# ODB21.net
KiCad netlist of a schematic drawn in EAGLE
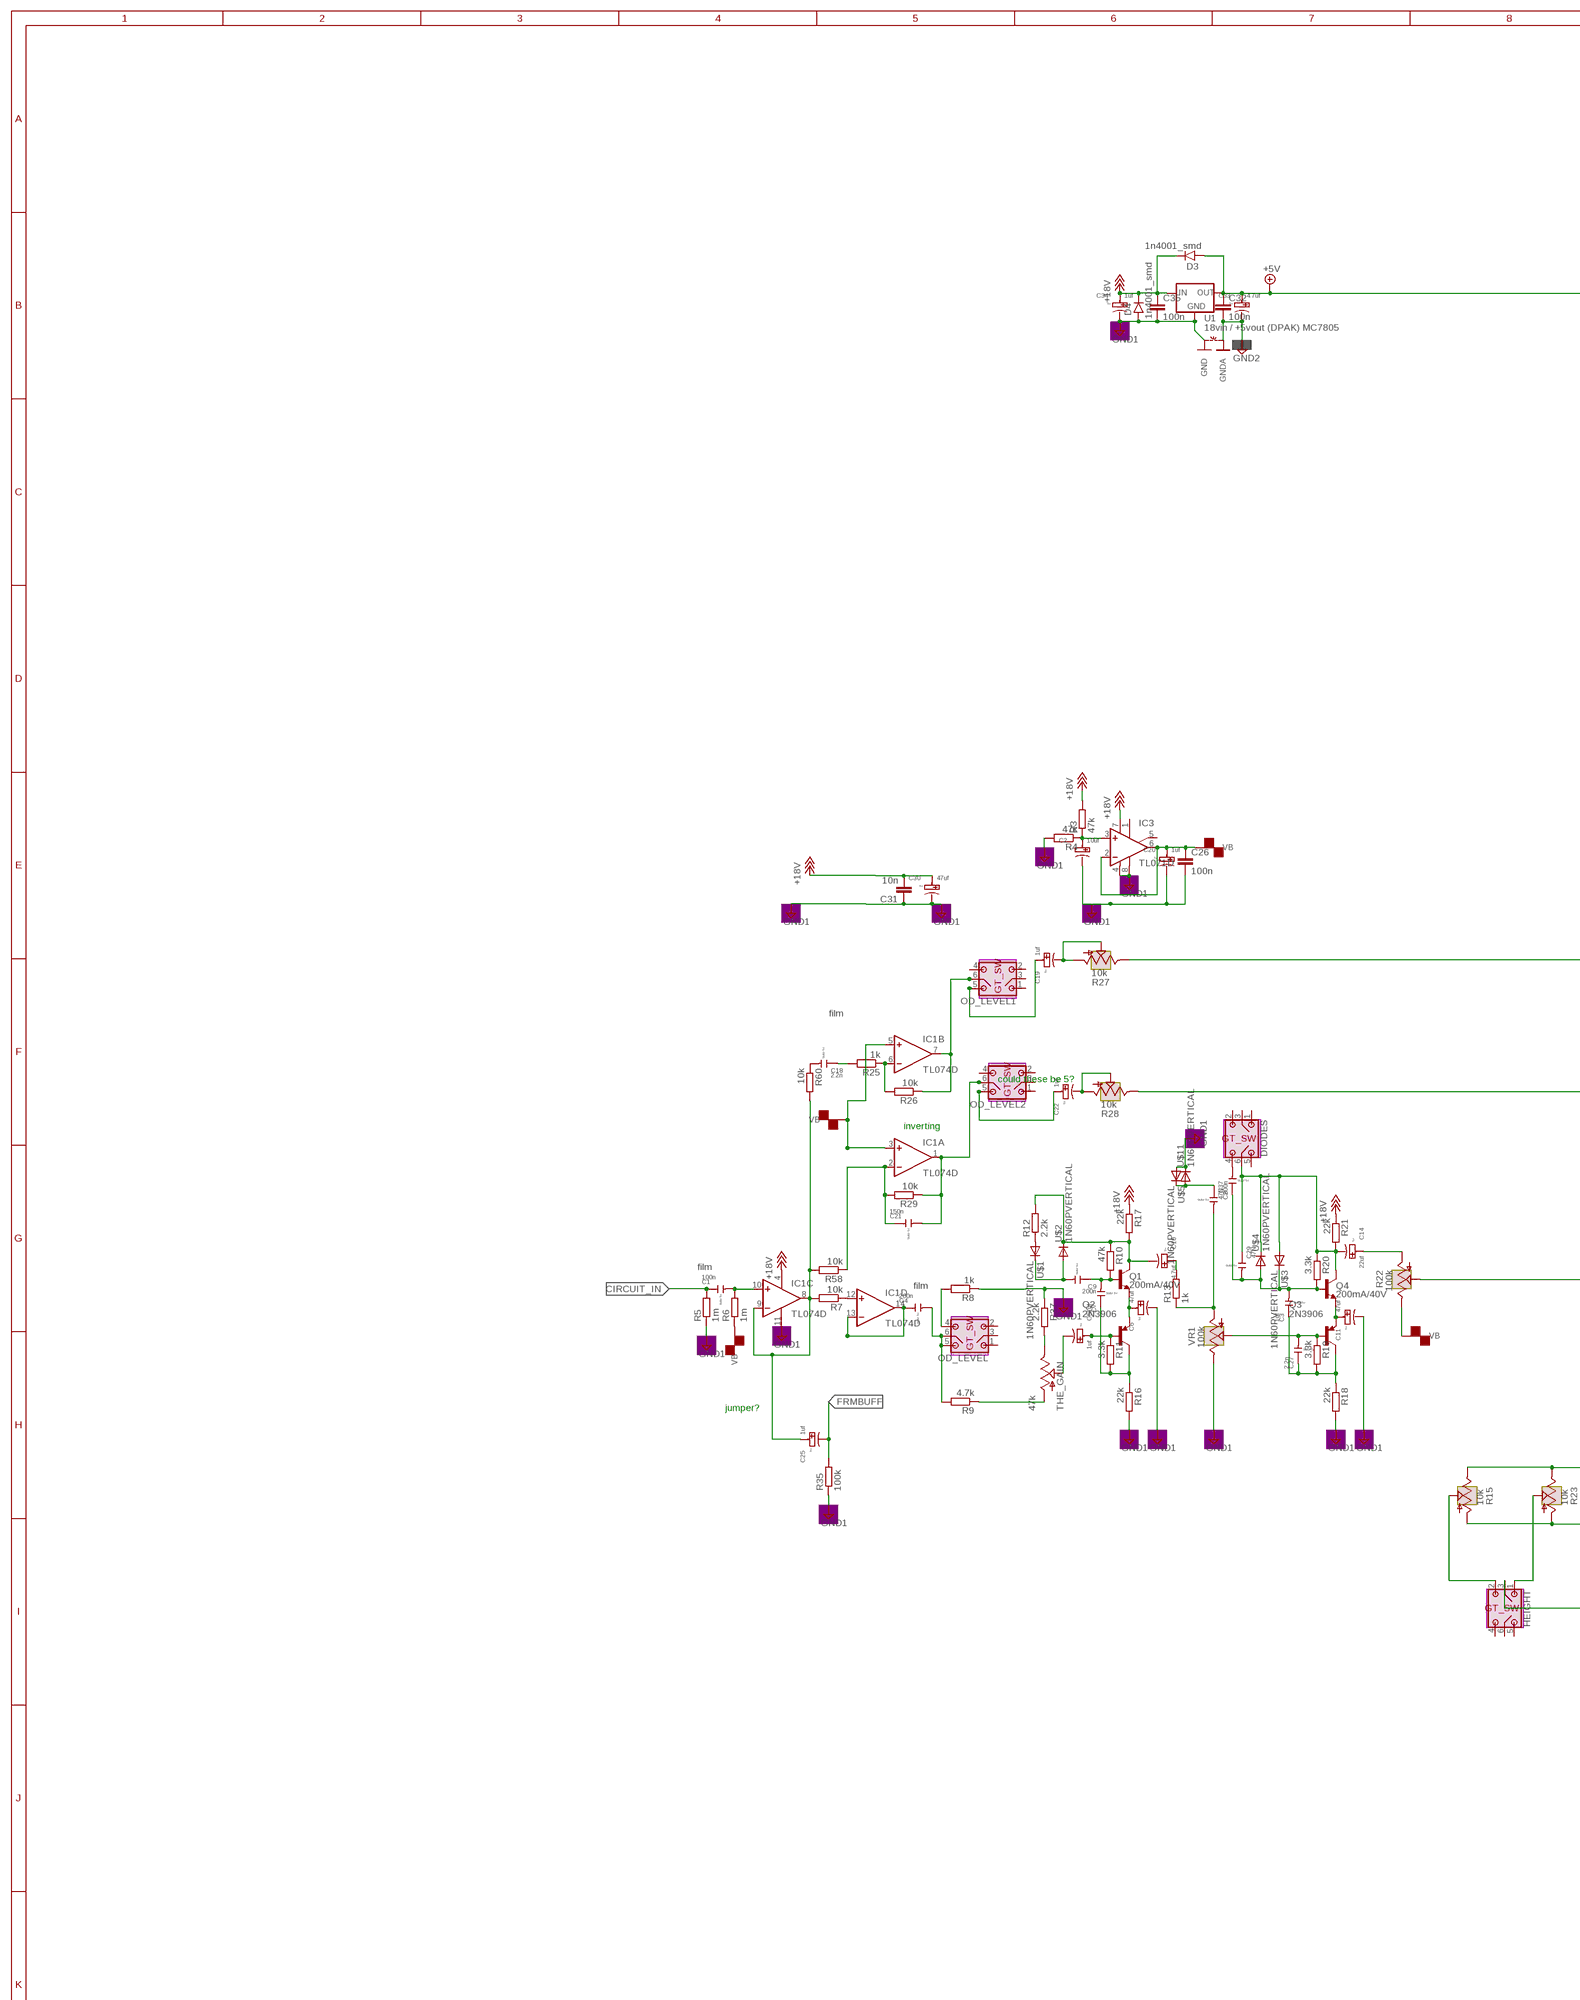
[diagram p0: schematic, sheet 1, part 1 of 3]
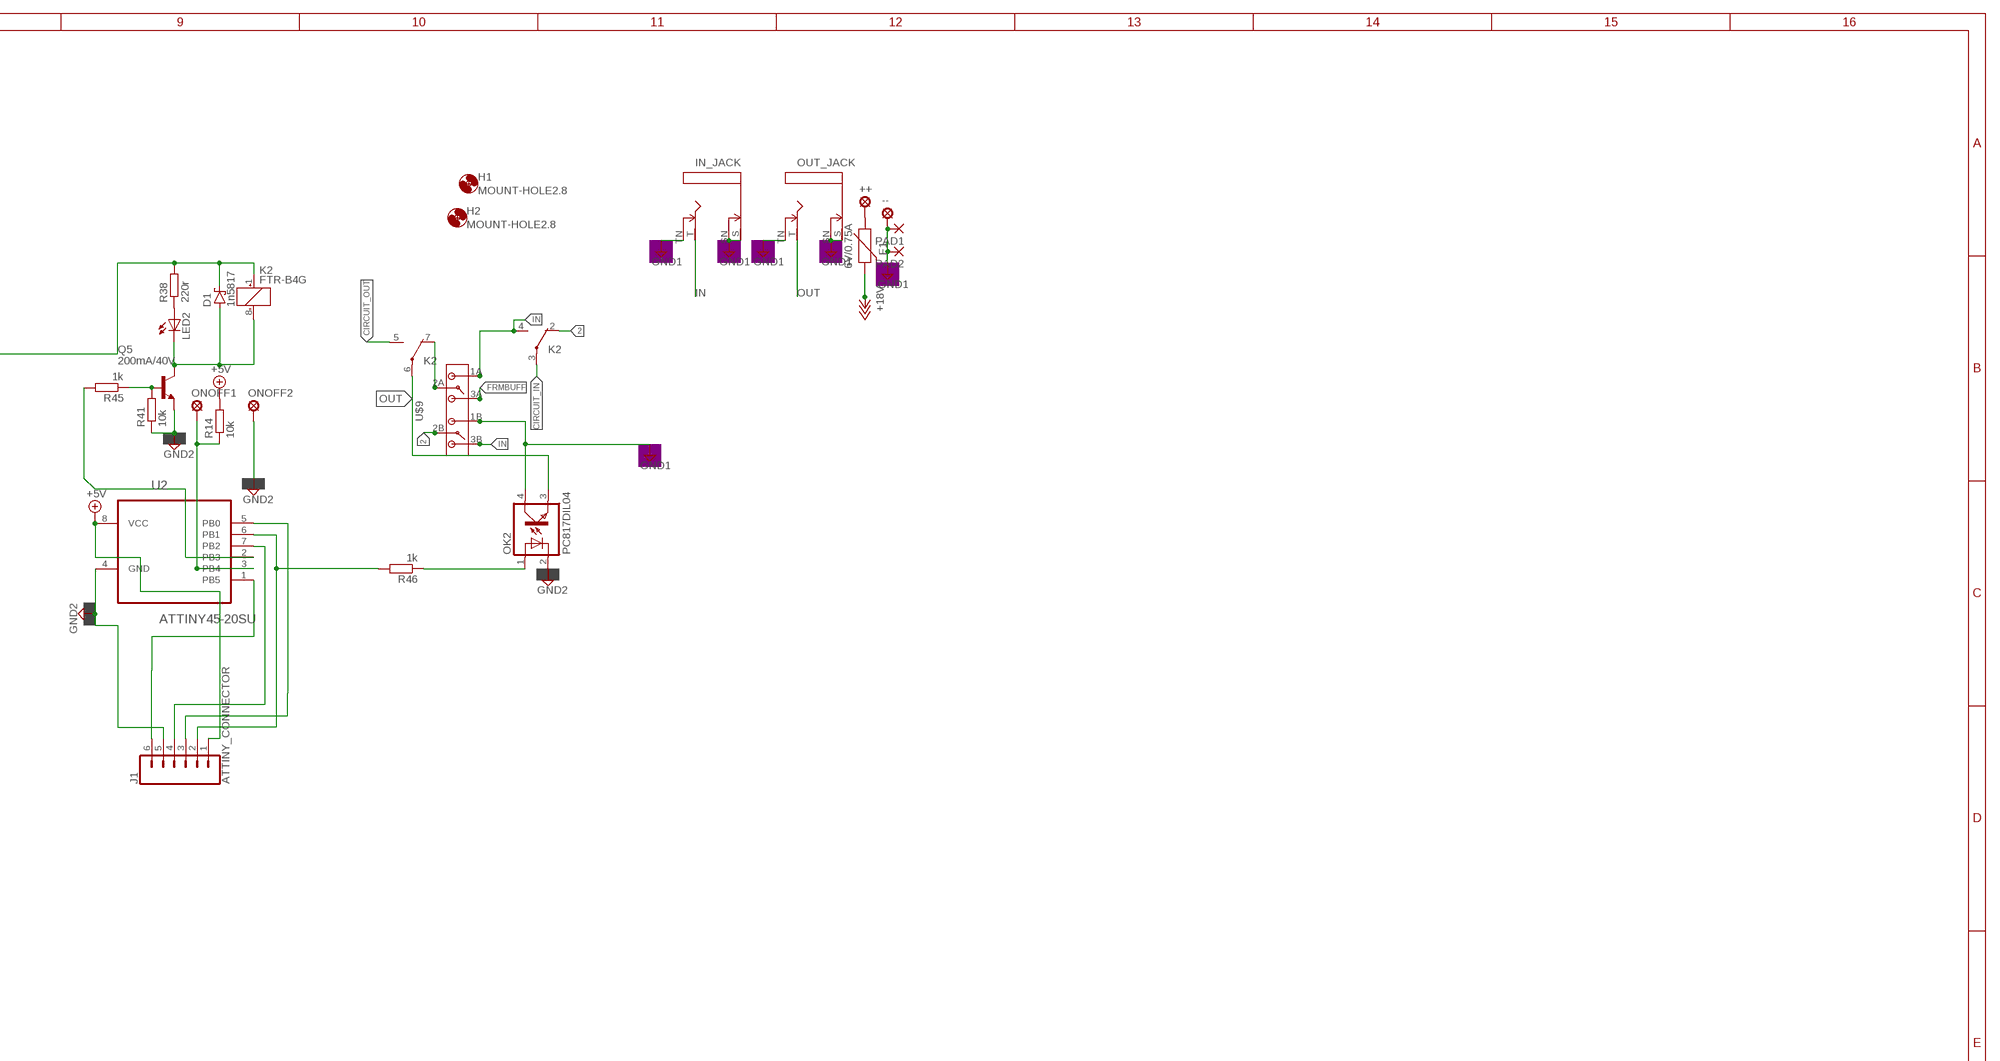
[diagram p1: schematic, sheet 1, part 2 of 3]
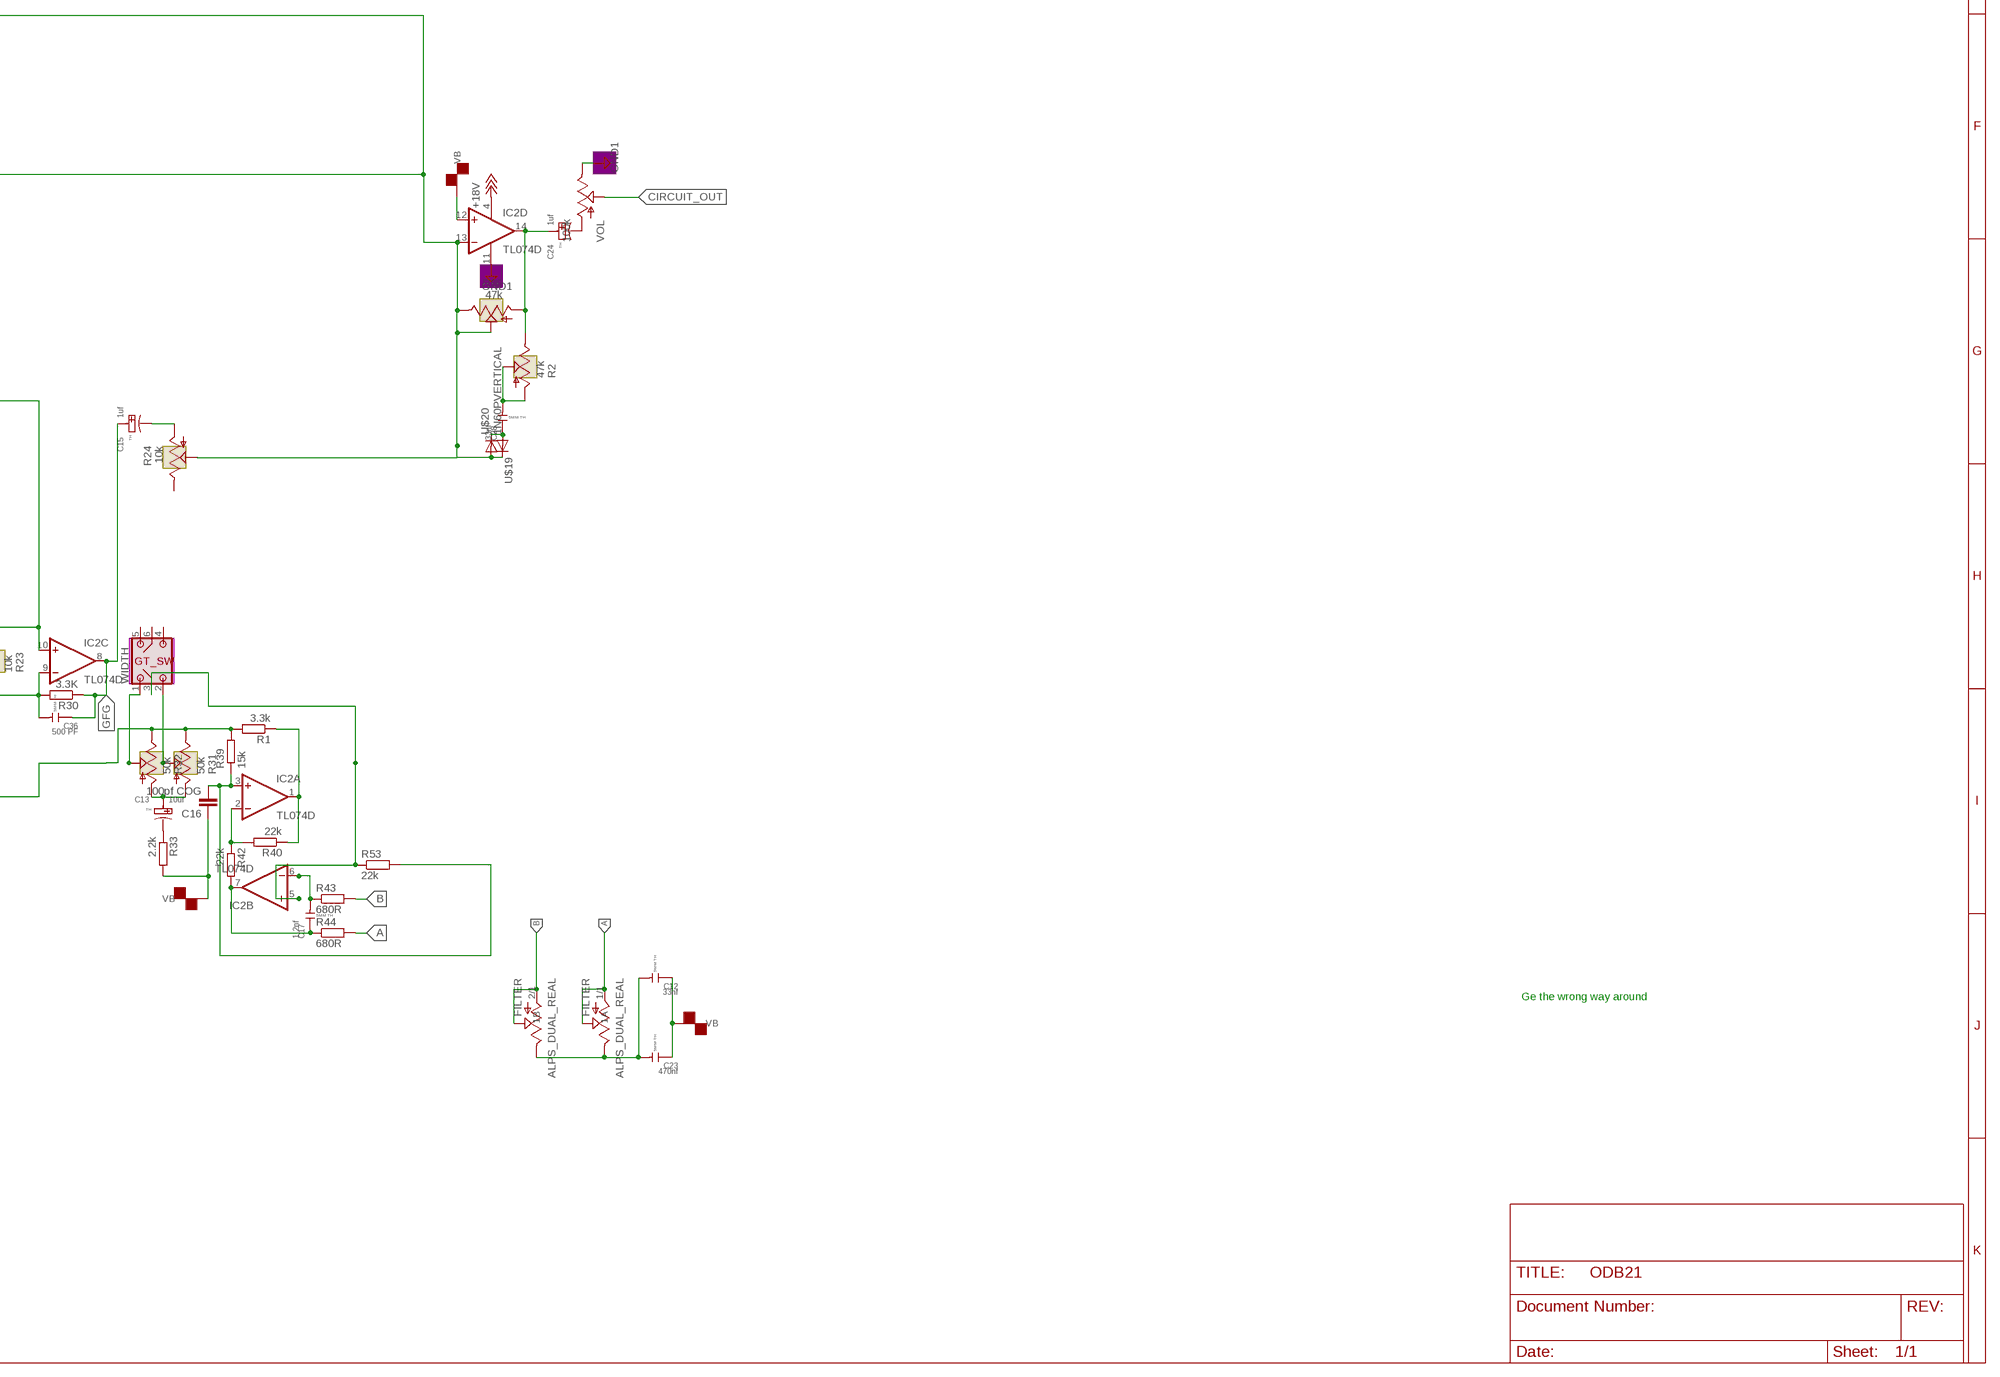
[diagram p2: schematic, sheet 1, part 3 of 3]

(export (version "E")
  (design (tool "Eeschema 10.0.6"))
  (components
    (comp (ref "++")
      (value "LSP10")
      (footprint "eagle-import:LSP10")
      (libsource (lib "eagle-import") (part "LSP10"))
    )
    (comp (ref "--")
      (value "LSP10")
      (footprint "eagle-import:LSP10")
      (libsource (lib "eagle-import") (part "LSP10"))
    )
    (comp (ref "C1")
      (value "100n")
      (footprint "eagle-import:CERAMIC-5MM")
      (fields (field (name "PACKAGE") "5MM TH"))
      (libsource (lib "eagle-import") (part "THRU_HOLE_5MM_SPACING"))
    )
    (comp (ref "C2")
      (value "10uf")
      (footprint "eagle-import:PC-D5.3MM")
      (fields (field (name "PACKAGE") "TH"))
      (libsource (lib "eagle-import") (part "THRU-HOLE-POLARIZED"))
    )
    (comp (ref "C3")
      (value "1uf")
      (footprint "eagle-import:CERAMIC-5MM")
      (fields (field (name "PACKAGE") "5MM TH"))
      (libsource (lib "eagle-import") (part "THRU_HOLE_5MM_SPACING"))
    )
    (comp (ref "C4")
      (value "200n")
      (footprint "eagle-import:CERAMIC-5MM")
      (fields (field (name "PACKAGE") "5MM TH"))
      (libsource (lib "eagle-import") (part "THRU_HOLE_5MM_SPACING"))
    )
    (comp (ref "C5")
      (value "1uf")
      (footprint "eagle-import:PC-D5.3MM")
      (fields (field (name "PACKAGE") "TH"))
      (libsource (lib "eagle-import") (part "THRU-HOLE-POLARIZED"))
    )
    (comp (ref "C6")
      (value "47uf")
      (footprint "eagle-import:PC-D5.3MM")
      (fields (field (name "PACKAGE") "TH"))
      (libsource (lib "eagle-import") (part "THRU-HOLE-POLARIZED"))
    )
    (comp (ref "C7")
      (value "1uf")
      (footprint "eagle-import:CERAMIC-5MM")
      (fields (field (name "PACKAGE") "5MM TH"))
      (libsource (lib "eagle-import") (part "THRU_HOLE_5MM_SPACING"))
    )
    (comp (ref "C8")
      (value "47N")
      (footprint "eagle-import:CERAMIC-5MM")
      (fields (field (name "PACKAGE") "5MM TH"))
      (libsource (lib "eagle-import") (part "THRU_HOLE_5MM_SPACING"))
    )
    (comp (ref "C9")
      (value "200n")
      (footprint "eagle-import:CERAMIC-5MM")
      (fields (field (name "PACKAGE") "5MM TH"))
      (libsource (lib "eagle-import") (part "THRU_HOLE_5MM_SPACING"))
    )
    (comp (ref "C10")
      (value "4.7uf")
      (footprint "eagle-import:PC-D5.3MM")
      (fields (field (name "PACKAGE") "TH"))
      (libsource (lib "eagle-import") (part "THRU-HOLE-POLARIZED"))
    )
    (comp (ref "C11")
      (value "47uf")
      (footprint "eagle-import:PC-D5.3MM")
      (fields (field (name "PACKAGE") "TH"))
      (libsource (lib "eagle-import") (part "THRU-HOLE-POLARIZED"))
    )
    (comp (ref "C12")
      (value "33nf")
      (footprint "eagle-import:CERAMIC-5MM")
      (fields (field (name "PACKAGE") "5MM TH"))
      (libsource (lib "eagle-import") (part "THRU_HOLE_5MM_SPACING"))
    )
    (comp (ref "C13")
      (value "10uf")
      (footprint "eagle-import:PC-D5.3MM")
      (fields (field (name "PACKAGE") "TH"))
      (libsource (lib "eagle-import") (part "THRU-HOLE-POLARIZED"))
    )
    (comp (ref "C14")
      (value "22uf")
      (footprint "eagle-import:PC-D5.3MM")
      (fields (field (name "PACKAGE") "TH"))
      (libsource (lib "eagle-import") (part "THRU-HOLE-POLARIZED"))
    )
    (comp (ref "C15")
      (value "1uf")
      (footprint "eagle-import:PC-D5.3MM")
      (fields (field (name "PACKAGE") "TH"))
      (libsource (lib "eagle-import") (part "THRU-HOLE-POLARIZED"))
    )
    (comp (ref "C16")
      (value "100pf COG")
      (footprint "eagle-import:C1206")
      (libsource (lib "eagle-import") (part "resistor_348_C-EUC1206"))
    )
    (comp (ref "C17")
      (value "1.2nf")
      (footprint "eagle-import:CERAMIC-5MM")
      (fields (field (name "PACKAGE") "5MM TH"))
      (libsource (lib "eagle-import") (part "THRU_HOLE_5MM_SPACING"))
    )
    (comp (ref "C18")
      (value "2.2n")
      (footprint "eagle-import:CERAMIC-5MM")
      (fields (field (name "PACKAGE") "5MM TH"))
      (libsource (lib "eagle-import") (part "THRU_HOLE_5MM_SPACING"))
    )
    (comp (ref "C19")
      (value "1uf")
      (footprint "eagle-import:PC-D5.3MM")
      (fields (field (name "PACKAGE") "TH"))
      (libsource (lib "eagle-import") (part "THRU-HOLE-POLARIZED"))
    )
    (comp (ref "C20")
      (value "1uf")
      (footprint "eagle-import:PC-D5.3MM")
      (fields (field (name "PACKAGE") "TH"))
      (libsource (lib "eagle-import") (part "THRU-HOLE-POLARIZED"))
    )
    (comp (ref "C21")
      (value "150n")
      (footprint "eagle-import:CERAMIC-5MM")
      (fields (field (name "PACKAGE") "5MM TH"))
      (libsource (lib "eagle-import") (part "THRU_HOLE_5MM_SPACING"))
    )
    (comp (ref "C22")
      (value "1uf")
      (footprint "eagle-import:PC-D5.3MM")
      (fields (field (name "PACKAGE") "TH"))
      (libsource (lib "eagle-import") (part "THRU-HOLE-POLARIZED"))
    )
    (comp (ref "C23")
      (value "470nf")
      (footprint "eagle-import:CERAMIC-5MM")
      (fields (field (name "PACKAGE") "5MM TH"))
      (libsource (lib "eagle-import") (part "THRU_HOLE_5MM_SPACING"))
    )
    (comp (ref "C24")
      (value "1uf")
      (footprint "eagle-import:PC-D5.3MM")
      (fields (field (name "PACKAGE") "TH"))
      (libsource (lib "eagle-import") (part "THRU-HOLE-POLARIZED"))
    )
    (comp (ref "C25")
      (value "1uf")
      (footprint "eagle-import:PC-D5.3MM")
      (fields (field (name "PACKAGE") "TH"))
      (libsource (lib "eagle-import") (part "THRU-HOLE-POLARIZED"))
    )
    (comp (ref "C26")
      (value "100n")
      (footprint "eagle-import:C1206")
      (libsource (lib "eagle-import") (part "resistor_348_C-EUC1206"))
    )
    (comp (ref "C27")
      (value "2.2n")
      (footprint "eagle-import:CERAMIC-5MM")
      (fields (field (name "PACKAGE") "5MM TH"))
      (libsource (lib "eagle-import") (part "THRU_HOLE_5MM_SPACING"))
    )
    (comp (ref "C28")
      (value "33nf")
      (footprint "eagle-import:CERAMIC-5MM")
      (fields (field (name "PACKAGE") "5MM TH"))
      (libsource (lib "eagle-import") (part "THRU_HOLE_5MM_SPACING"))
    )
    (comp (ref "C29")
      (value "47N")
      (footprint "eagle-import:CERAMIC-5MM")
      (fields (field (name "PACKAGE") "5MM TH"))
      (libsource (lib "eagle-import") (part "THRU_HOLE_5MM_SPACING"))
    )
    (comp (ref "C30")
      (value "47uf")
      (footprint "eagle-import:PC-D5.3MM")
      (fields (field (name "PACKAGE") "TH"))
      (libsource (lib "eagle-import") (part "THRU-HOLE-POLARIZED"))
    )
    (comp (ref "C31")
      (value "10n")
      (footprint "eagle-import:C1206")
      (libsource (lib "eagle-import") (part "C-EUC1206"))
    )
    (comp (ref "C32")
      (value "100n")
      (footprint "eagle-import:C1206")
      (libsource (lib "eagle-import") (part "resistor_348_C-EUC1206"))
    )
    (comp (ref "C33")
      (value "4.7uf")
      (footprint "eagle-import:PC-D5.3MM")
      (fields (field (name "PACKAGE") "TH"))
      (libsource (lib "eagle-import") (part "THRU-HOLE-POLARIZED"))
    )
    (comp (ref "C34")
      (value "1uf")
      (footprint "eagle-import:PC-D5.3MM")
      (fields (field (name "PACKAGE") "TH"))
      (libsource (lib "eagle-import") (part "THRU-HOLE-POLARIZED"))
    )
    (comp (ref "C35")
      (value "100n")
      (footprint "eagle-import:C1206")
      (libsource (lib "eagle-import") (part "resistor_348_C-EUC1206"))
    )
    (comp (ref "C36")
      (value "500 PF")
      (footprint "eagle-import:CERAMIC-5MM")
      (fields (field (name "PACKAGE") "5MM TH"))
      (libsource (lib "eagle-import") (part "THRU_HOLE_5MM_SPACING"))
    )
    (comp (ref "C37")
      (value "200n")
      (footprint "eagle-import:CERAMIC-5MM")
      (fields (field (name "PACKAGE") "5MM TH"))
      (libsource (lib "eagle-import") (part "THRU_HOLE_5MM_SPACING"))
    )
    (comp (ref "D1")
      (value "1n5817")
      (footprint "eagle-import:SMB")
      (libsource (lib "eagle-import") (part "SCHOTTKY-DIODESMD"))
    )
    (comp (ref "D3")
      (value "1n4001_smd")
      (footprint "eagle-import:DO41-1")
      (libsource (lib "eagle-import") (part "1N400X.1"))
    )
    (comp (ref "D4")
      (value "1n4001_smd")
      (footprint "eagle-import:DO41-1")
      (libsource (lib "eagle-import") (part "1N400X.1"))
    )
    (comp (ref "DIODES")
      (value "DP03")
      (footprint "eagle-import:DP-03")
      (fields (field (name "MPN") "MCDP03"))
      (libsource (lib "eagle-import") (part "DP03"))
    )
    (comp (ref "F1")
      (value "6V/0.75A")
      (footprint "eagle-import:1206")
      (libsource (lib "eagle-import") (part "PPTC_THREE-QUARTER-AMP"))
    )
    (comp (ref "FILTER")
      (value "ALPS_DUAL_REAL")
      (footprint "eagle-import:ALPS_QUAD")
      (libsource (lib "eagle-import") (part "ALPS_DUAL_REAL"))
    )
    (comp (ref "H1")
      (value "MOUNT-HOLE2.8")
      (footprint "eagle-import:2,8")
      (libsource (lib "eagle-import") (part "MOUNT-HOLE2.8"))
    )
    (comp (ref "H2")
      (value "MOUNT-HOLE2.8")
      (footprint "eagle-import:2,8")
      (libsource (lib "eagle-import") (part "MOUNT-HOLE2.8"))
    )
    (comp (ref "HEIGHT")
      (value "DP03")
      (footprint "eagle-import:DP-03")
      (fields (field (name "MPN") "MCDP03"))
      (libsource (lib "eagle-import") (part "DP03"))
    )
    (comp (ref "IC1")
      (value "TL074D")
      (footprint "eagle-import:SO14")
      (libsource (lib "eagle-import") (part "TL074D"))
    )
    (comp (ref "IC2")
      (value "TL074D")
      (footprint "eagle-import:SO14")
      (libsource (lib "eagle-import") (part "TL074D"))
    )
    (comp (ref "IC3")
      (value "TL071D")
      (footprint "eagle-import:SO08")
      (libsource (lib "eagle-import") (part "TL071D"))
    )
    (comp (ref "IN_JACK")
      (value "MMMONNN")
      (footprint "eagle-import:MONO")
      (libsource (lib "eagle-import") (part "MMMONNN"))
    )
    (comp (ref "J1")
      (value "ATTINY_CONNECTOR")
      (footprint "eagle-import:1X06_LONGPADS")
      (libsource (lib "eagle-import") (part "CONN_06LONGPADS"))
    )
    (comp (ref "K2")
      (value "FTR-B4G")
      (footprint "eagle-import:FTR-B4G")
      (libsource (lib "eagle-import") (part "FTR-B4G"))
    )
    (comp (ref "LED2")
      (value "LED3MM")
      (footprint "eagle-import:LED3MM")
      (libsource (lib "eagle-import") (part "LED3MM"))
    )
    (comp (ref "OD_LEVEL")
      (value "DP03")
      (footprint "eagle-import:DP-03")
      (fields (field (name "MPN") "MCDP03"))
      (libsource (lib "eagle-import") (part "DP03"))
    )
    (comp (ref "OD_LEVEL1")
      (value "DP03")
      (footprint "eagle-import:DP-03")
      (fields (field (name "MPN") "MCDP03"))
      (libsource (lib "eagle-import") (part "DP03"))
    )
    (comp (ref "OD_LEVEL2")
      (value "DP03")
      (footprint "eagle-import:DP-03")
      (fields (field (name "MPN") "MCDP03"))
      (libsource (lib "eagle-import") (part "DP03"))
    )
    (comp (ref "OK2")
      (value "PC817DIL04")
      (footprint "eagle-import:SMD4")
      (libsource (lib "eagle-import") (part "PC817DIL04"))
    )
    (comp (ref "ONOFF1")
      (value "LSP10")
      (footprint "eagle-import:LSP10")
      (libsource (lib "eagle-import") (part "LSP10"))
    )
    (comp (ref "ONOFF2")
      (value "LSP10")
      (footprint "eagle-import:LSP10")
      (libsource (lib "eagle-import") (part "LSP10"))
    )
    (comp (ref "OUT_JACK")
      (value "MMMONNN")
      (footprint "eagle-import:MONO")
      (libsource (lib "eagle-import") (part "MMMONNN"))
    )
    (comp (ref "PAD1")
      (value "SMD5")
      (footprint "eagle-import:SMD2,54-5,08")
      (libsource (lib "eagle-import") (part "SMD5"))
    )
    (comp (ref "PAD2")
      (value "SMD5")
      (footprint "eagle-import:SMD2,54-5,08")
      (libsource (lib "eagle-import") (part "SMD5"))
    )
    (comp (ref "Q1")
      (value "200mA/40V")
      (footprint "eagle-import:TO-92")
      (libsource (lib "eagle-import") (part "TRANS_NPN-2N3904"))
    )
    (comp (ref "Q2")
      (value "2N3906")
      (footprint "eagle-import:TO92")
      (libsource (lib "eagle-import") (part "2N3906"))
    )
    (comp (ref "Q3")
      (value "2N3906")
      (footprint "eagle-import:TO92")
      (libsource (lib "eagle-import") (part "2N3906"))
    )
    (comp (ref "Q4")
      (value "200mA/40V")
      (footprint "eagle-import:TO-92")
      (libsource (lib "eagle-import") (part "TRANS_NPN-2N3904"))
    )
    (comp (ref "Q5")
      (value "200mA/40V")
      (footprint "eagle-import:TO92")
      (libsource (lib "eagle-import") (part "BC547"))
    )
    (comp (ref "R1")
      (value "3.3k")
      (footprint "eagle-import:R1206")
      (libsource (lib "eagle-import") (part "R-EU_R1206"))
    )
    (comp (ref "R2")
      (value "47k")
      (footprint "eagle-import:B25P")
      (libsource (lib "eagle-import") (part "TRIM_US-B25P"))
    )
    (comp (ref "R3")
      (value "47k")
      (footprint "eagle-import:R1206")
      (libsource (lib "eagle-import") (part "R-EU_R1206"))
    )
    (comp (ref "R4")
      (value "47k")
      (footprint "eagle-import:R1206")
      (libsource (lib "eagle-import") (part "R-EU_R1206"))
    )
    (comp (ref "R5")
      (value "1m")
      (footprint "eagle-import:R1206")
      (libsource (lib "eagle-import") (part "R-EU_R1206"))
    )
    (comp (ref "R6")
      (value "1m")
      (footprint "eagle-import:R1206")
      (libsource (lib "eagle-import") (part "R-EU_R1206"))
    )
    (comp (ref "R7")
      (value "10k")
      (footprint "eagle-import:R1206")
      (libsource (lib "eagle-import") (part "R-EU_R1206"))
    )
    (comp (ref "R8")
      (value "1k")
      (footprint "eagle-import:R1206")
      (libsource (lib "eagle-import") (part "R-EU_R1206"))
    )
    (comp (ref "R9")
      (value "4.7k")
      (footprint "eagle-import:R1206")
      (libsource (lib "eagle-import") (part "R-EU_R1206"))
    )
    (comp (ref "R10")
      (value "47k")
      (footprint "eagle-import:R1206")
      (libsource (lib "eagle-import") (part "R-EU_R1206"))
    )
    (comp (ref "R11")
      (value "3.3k")
      (footprint "eagle-import:R1206")
      (libsource (lib "eagle-import") (part "R-EU_R1206"))
    )
    (comp (ref "R12")
      (value "2.2k")
      (footprint "eagle-import:R1206")
      (libsource (lib "eagle-import") (part "R-EU_R1206"))
    )
    (comp (ref "R13")
      (value "1k")
      (footprint "eagle-import:R1206")
      (libsource (lib "eagle-import") (part "R-EU_R1206"))
    )
    (comp (ref "R14")
      (value "10k")
      (footprint "eagle-import:M1206")
      (libsource (lib "eagle-import") (part "R-EU_M1206"))
    )
    (comp (ref "R15")
      (value "10k")
      (footprint "eagle-import:3223G")
      (libsource (lib "eagle-import") (part "TRIM_US-3223G"))
    )
    (comp (ref "R16")
      (value "22k")
      (footprint "eagle-import:R1206")
      (libsource (lib "eagle-import") (part "R-EU_R1206"))
    )
    (comp (ref "R17")
      (value "22k")
      (footprint "eagle-import:R1206")
      (libsource (lib "eagle-import") (part "R-EU_R1206"))
    )
    (comp (ref "R18")
      (value "22k")
      (footprint "eagle-import:R1206")
      (libsource (lib "eagle-import") (part "R-EU_R1206"))
    )
    (comp (ref "R19")
      (value "3.3k")
      (footprint "eagle-import:R1206")
      (libsource (lib "eagle-import") (part "R-EU_R1206"))
    )
    (comp (ref "R20")
      (value "3.3k")
      (footprint "eagle-import:R1206")
      (libsource (lib "eagle-import") (part "R-EU_R1206"))
    )
    (comp (ref "R21")
      (value "22k")
      (footprint "eagle-import:R1206")
      (libsource (lib "eagle-import") (part "R-EU_R1206"))
    )
    (comp (ref "R22")
      (value "100k")
      (footprint "eagle-import:3223G")
      (libsource (lib "eagle-import") (part "TRIM_US-3223G"))
    )
    (comp (ref "R23")
      (value "10k")
      (footprint "eagle-import:3223G")
      (libsource (lib "eagle-import") (part "TRIM_US-3223G"))
    )
    (comp (ref "R24")
      (value "10k")
      (footprint "eagle-import:3223G")
      (libsource (lib "eagle-import") (part "TRIM_US-3223G"))
    )
    (comp (ref "R25")
      (value "1k")
      (footprint "eagle-import:R1206")
      (libsource (lib "eagle-import") (part "R-EU_R1206"))
    )
    (comp (ref "R26")
      (value "10k")
      (footprint "eagle-import:R1206")
      (libsource (lib "eagle-import") (part "R-EU_R1206"))
    )
    (comp (ref "R27")
      (value "10k")
      (footprint "eagle-import:3223G")
      (libsource (lib "eagle-import") (part "TRIM_US-3223G"))
    )
    (comp (ref "R28")
      (value "10k")
      (footprint "eagle-import:3223G")
      (libsource (lib "eagle-import") (part "TRIM_US-3223G"))
    )
    (comp (ref "R29")
      (value "10k")
      (footprint "eagle-import:R1206")
      (libsource (lib "eagle-import") (part "R-EU_R1206"))
    )
    (comp (ref "R30")
      (value "3.3K")
      (footprint "eagle-import:R1206")
      (libsource (lib "eagle-import") (part "R-EU_R1206"))
    )
    (comp (ref "R31")
      (value "50k")
      (footprint "eagle-import:3223G")
      (libsource (lib "eagle-import") (part "TRIM_US-3223G"))
    )
    (comp (ref "R32")
      (value "50k")
      (footprint "eagle-import:3223G")
      (libsource (lib "eagle-import") (part "TRIM_US-3223G"))
    )
    (comp (ref "R33")
      (value "2.2k")
      (footprint "eagle-import:R1206")
      (libsource (lib "eagle-import") (part "R-EU_R1206"))
    )
    (comp (ref "R35")
      (value "100k")
      (footprint "eagle-import:R1206")
      (libsource (lib "eagle-import") (part "R-EU_R1206"))
    )
    (comp (ref "R36")
      (value "47k")
      (footprint "eagle-import:3223G")
      (libsource (lib "eagle-import") (part "TRIM_US-3223G"))
    )
    (comp (ref "R37")
      (value "2.2k")
      (footprint "eagle-import:R1206")
      (libsource (lib "eagle-import") (part "R-EU_R1206"))
    )
    (comp (ref "R38")
      (value "220r")
      (footprint "eagle-import:M1206")
      (libsource (lib "eagle-import") (part "R-EU_M1206"))
    )
    (comp (ref "R39")
      (value "15k")
      (footprint "eagle-import:R1206")
      (libsource (lib "eagle-import") (part "R-EU_R1206"))
    )
    (comp (ref "R40")
      (value "22k")
      (footprint "eagle-import:R1206")
      (libsource (lib "eagle-import") (part "R-EU_R1206"))
    )
    (comp (ref "R41")
      (value "10k")
      (footprint "eagle-import:M1206")
      (libsource (lib "eagle-import") (part "R-EU_M1206"))
    )
    (comp (ref "R42")
      (value "22k")
      (footprint "eagle-import:R1206")
      (libsource (lib "eagle-import") (part "R-EU_R1206"))
    )
    (comp (ref "R43")
      (value "680R")
      (footprint "eagle-import:R1206")
      (libsource (lib "eagle-import") (part "R-EU_R1206"))
    )
    (comp (ref "R44")
      (value "680R")
      (footprint "eagle-import:R1206")
      (libsource (lib "eagle-import") (part "R-EU_R1206"))
    )
    (comp (ref "R45")
      (value "1k")
      (footprint "eagle-import:M1206")
      (libsource (lib "eagle-import") (part "R-EU_M1206"))
    )
    (comp (ref "R46")
      (value "1k")
      (footprint "eagle-import:M1206")
      (libsource (lib "eagle-import") (part "R-EU_M1206"))
    )
    (comp (ref "R53")
      (value "22k")
      (footprint "eagle-import:R1206")
      (libsource (lib "eagle-import") (part "R-EU_R1206"))
    )
    (comp (ref "R58")
      (value "10k")
      (footprint "eagle-import:R1206")
      (libsource (lib "eagle-import") (part "R-EU_R1206"))
    )
    (comp (ref "R60")
      (value "10k")
      (footprint "eagle-import:R1206")
      (libsource (lib "eagle-import") (part "R-EU_R1206"))
    )
    (comp (ref "THE_GAIN")
      (value "47k")
      (footprint "eagle-import:ALPS_POT")
      (libsource (lib "eagle-import") (part "POT"))
    )
    (comp (ref "U$1")
      (value "1N60PVERTICAL")
      (footprint "eagle-import:DO41-1")
      (libsource (lib "eagle-import") (part "1N60PVERTICAL"))
    )
    (comp (ref "U$2")
      (value "1N60PVERTICAL")
      (footprint "eagle-import:DO41-1")
      (libsource (lib "eagle-import") (part "1N60PVERTICAL"))
    )
    (comp (ref "U$3")
      (value "1N60PVERTICAL")
      (footprint "eagle-import:DO41-1")
      (libsource (lib "eagle-import") (part "1N60PVERTICAL"))
    )
    (comp (ref "U$4")
      (value "1N60PVERTICAL")
      (footprint "eagle-import:DO41-1")
      (libsource (lib "eagle-import") (part "1N60PVERTICAL"))
    )
    (comp (ref "U$5")
      (value "1N60PVERTICAL")
      (footprint "eagle-import:DO41-1")
      (libsource (lib "eagle-import") (part "1N60PVERTICAL"))
    )
    (comp (ref "U$9")
      (value "BYSWITCH")
      (footprint "eagle-import:BUFF_TRBYPASS")
      (libsource (lib "eagle-import") (part "BYSWITCH"))
    )
    (comp (ref "U$11")
      (value "1N60PVERTICAL")
      (footprint "eagle-import:DO41-1")
      (libsource (lib "eagle-import") (part "1N60PVERTICAL"))
    )
    (comp (ref "U$19")
      (value "1N60PVERTICAL")
      (footprint "eagle-import:DO41-1")
      (libsource (lib "eagle-import") (part "1N60PVERTICAL"))
    )
    (comp (ref "U$20")
      (value "1N60PVERTICAL")
      (footprint "eagle-import:DO41-1")
      (libsource (lib "eagle-import") (part "1N60PVERTICAL"))
    )
    (comp (ref "U1")
      (value "18vin / +5vout (DPAK) MC7805")
      (footprint "eagle-import:TO-252")
      (libsource (lib "eagle-import") (part "V_REG_78XX7812"))
    )
    (comp (ref "U2")
      (value "ATTINY45-20SU")
      (footprint "eagle-import:SOIC127P798X216-8N")
      (libsource (lib "eagle-import") (part "ATTINY45-20SU"))
    )
    (comp (ref "VOL")
      (value "100k")
      (footprint "eagle-import:ALPS_POT")
      (libsource (lib "eagle-import") (part "POT"))
    )
    (comp (ref "VR1")
      (value "100k")
      (footprint "eagle-import:3223G")
      (libsource (lib "eagle-import") (part "TRIM_US-3223G"))
    )
    (comp (ref "WIDTH")
      (value "DP03")
      (footprint "eagle-import:DP-03")
      (fields (field (name "MPN") "MCDP03"))
      (libsource (lib "eagle-import") (part "DP03"))
    )
    (comp (ref "~NUDEV~1")
      (value "GND-GNDA1,27MM")
      (footprint "eagle-import:GND-GNDA-1,27MM")
      (libsource (lib "eagle-import") (part "GND-GNDA1,27MM"))
    )
  )
  (nets
    (net (code "1") (name "+5V") (class "Default")
      (node (ref "C32") (pin "1") (pinfunction "1_1") (pintype "passive"))
      (node (ref "C33") (pin "+") (pinfunction "+_+") (pintype "passive"))
      (node (ref "D1") (pin "C") (pinfunction "C_C") (pintype "passive"))
      (node (ref "D3") (pin "A") (pinfunction "A_A") (pintype "passive"))
      (node (ref "J1") (pin "1") (pinfunction "1_1") (pintype "passive"))
      (node (ref "K2") (pin "1") (pinfunction "+_1") (pintype "passive"))
      (node (ref "R14") (pin "2") (pinfunction "2_2") (pintype "passive"))
      (node (ref "R38") (pin "2") (pinfunction "2_2") (pintype "passive"))
      (node (ref "U1") (pin "2") (pinfunction "OUT_2") (pintype "passive"))
      (node (ref "U2") (pin "8") (pinfunction "VCC_8") (pintype "power_in"))
    )
    (net (code "2") (name "+18V") (class "Default")
      (node (ref "C30") (pin "+") (pinfunction "+_+") (pintype "passive"))
      (node (ref "C31") (pin "2") (pinfunction "2_2") (pintype "passive"))
      (node (ref "C34") (pin "+") (pinfunction "+_+") (pintype "passive"))
      (node (ref "C35") (pin "1") (pinfunction "1_1") (pintype "passive"))
      (node (ref "D3") (pin "C") (pinfunction "C_C") (pintype "passive"))
      (node (ref "D4") (pin "C") (pinfunction "C_C") (pintype "passive"))
      (node (ref "F1") (pin "2") (pinfunction "2_2") (pintype "bidirectional"))
      (node (ref "IC1") (pin "4") (pinfunction "V+_4") (pintype "power_in"))
      (node (ref "IC2") (pin "4") (pinfunction "V+_4") (pintype "power_in"))
      (node (ref "IC3") (pin "7") (pinfunction "V+_7") (pintype "power_in"))
      (node (ref "R17") (pin "1") (pinfunction "1_1") (pintype "passive"))
      (node (ref "R21") (pin "1") (pinfunction "1_1") (pintype "passive"))
      (node (ref "R3") (pin "2") (pinfunction "2_2") (pintype "passive"))
      (node (ref "U1") (pin "1") (pinfunction "IN_1") (pintype "input"))
    )
    (net (code "3") (name "2") (class "Default")
      (node (ref "K2") (pin "2") (pinfunction "O_2") (pintype "passive"))
      (node (ref "U$9") (pin "2B") (pinfunction "2B_2B") (pintype "passive"))
    )
    (net (code "4") (name "A") (class "Default")
      (node (ref "FILTER") (pin "1/1") (pinfunction "1A_1/1") (pintype "passive"))
      (node (ref "FILTER") (pin "1/2") (pinfunction "2A_1/2") (pintype "passive"))
      (node (ref "R44") (pin "2") (pinfunction "2_2") (pintype "passive"))
    )
    (net (code "5") (name "B") (class "Default")
      (node (ref "FILTER") (pin "2/1") (pinfunction "1B_2/1") (pintype "passive"))
      (node (ref "FILTER") (pin "2/2") (pinfunction "2B_2/2") (pintype "passive"))
      (node (ref "R43") (pin "2") (pinfunction "2_2") (pintype "passive"))
    )
    (net (code "6") (name "CIRCUIT_IN") (class "Default")
      (node (ref "C1") (pin "1") (pinfunction "1_1") (pintype "passive"))
      (node (ref "K2") (pin "3") (pinfunction "P_3") (pintype "passive"))
      (node (ref "R5") (pin "2") (pinfunction "2_2") (pintype "passive"))
    )
    (net (code "7") (name "CIRCUIT_OUT") (class "Default")
      (node (ref "K2") (pin "5") (pinfunction "S_5") (pintype "passive"))
      (node (ref "VOL") (pin "P$2") (pinfunction "S_P$2") (pintype "passive"))
    )
    (net (code "8") (name "FRMBUFF") (class "Default")
      (node (ref "C25") (pin "-") (pinfunction "-_-") (pintype "passive"))
      (node (ref "R35") (pin "2") (pinfunction "2_2") (pintype "passive"))
      (node (ref "U$9") (pin "3A") (pinfunction "3A_3A") (pintype "passive"))
    )
    (net (code "9") (name "GFG") (class "Default")
      (node (ref "C15") (pin "+") (pinfunction "+_+") (pintype "passive"))
      (node (ref "C36") (pin "1") (pinfunction "1_1") (pintype "passive"))
      (node (ref "IC2") (pin "8") (pinfunction "OUT_8") (pintype "output"))
      (node (ref "R30") (pin "1") (pinfunction "1_1") (pintype "passive"))
    )
    (net (code "10") (name "GND1") (class "Default")
      (node (ref "--") (pin "MP") (pinfunction "MP_MP") (pintype "passive"))
      (node (ref "C11") (pin "-") (pinfunction "-_-") (pintype "passive"))
      (node (ref "C2") (pin "-") (pinfunction "-_-") (pintype "passive"))
      (node (ref "C20") (pin "-") (pinfunction "-_-") (pintype "passive"))
      (node (ref "C26") (pin "2") (pinfunction "2_2") (pintype "passive"))
      (node (ref "C30") (pin "-") (pinfunction "-_-") (pintype "passive"))
      (node (ref "C31") (pin "1") (pinfunction "1_1") (pintype "passive"))
      (node (ref "C34") (pin "-") (pinfunction "-_-") (pintype "passive"))
      (node (ref "C35") (pin "2") (pinfunction "2_2") (pintype "passive"))
      (node (ref "C6") (pin "-") (pinfunction "-_-") (pintype "passive"))
      (node (ref "D4") (pin "A") (pinfunction "A_A") (pintype "passive"))
      (node (ref "IC1") (pin "11") (pinfunction "V-_11") (pintype "power_in"))
      (node (ref "IC2") (pin "11") (pinfunction "V-_11") (pintype "power_in"))
      (node (ref "IC3") (pin "4") (pinfunction "V-_4") (pintype "power_in"))
      (node (ref "IC3") (pin "8") (pinfunction "OPT_8") (pintype "passive"))
      (node (ref "IN_JACK") (pin "S") (pinfunction "S_S") (pintype "passive"))
      (node (ref "IN_JACK") (pin "SN") (pinfunction "SN_SN") (pintype "passive"))
      (node (ref "IN_JACK") (pin "TN") (pinfunction "TN_TN") (pintype "passive"))
      (node (ref "OK2") (pin "4") (pinfunction "COL_4") (pintype "passive"))
      (node (ref "OUT_JACK") (pin "S") (pinfunction "S_S") (pintype "passive"))
      (node (ref "OUT_JACK") (pin "SN") (pinfunction "SN_SN") (pintype "passive"))
      (node (ref "OUT_JACK") (pin "TN") (pinfunction "TN_TN") (pintype "passive"))
      (node (ref "PAD1") (pin "1") (pinfunction "P_1") (pintype "passive"))
      (node (ref "PAD2") (pin "1") (pinfunction "P_1") (pintype "passive"))
      (node (ref "R16") (pin "2") (pinfunction "2_2") (pintype "passive"))
      (node (ref "R18") (pin "2") (pinfunction "2_2") (pintype "passive"))
      (node (ref "R35") (pin "1") (pinfunction "1_1") (pintype "passive"))
      (node (ref "R37") (pin "1") (pinfunction "1_1") (pintype "passive"))
      (node (ref "R4") (pin "2") (pinfunction "2_2") (pintype "passive"))
      (node (ref "R5") (pin "1") (pinfunction "1_1") (pintype "passive"))
      (node (ref "R8") (pin "1") (pinfunction "1_1") (pintype "passive"))
      (node (ref "U$11") (pin "C") (pinfunction "C_C") (pintype "passive"))
      (node (ref "U$5") (pin "A") (pinfunction "A_A") (pintype "passive"))
      (node (ref "U$9") (pin "1B") (pinfunction "1B_1B") (pintype "passive"))
      (node (ref "U1") (pin "3") (pinfunction "GND_3") (pintype "input"))
      (node (ref "VOL") (pin "P$1") (pinfunction "E_P$1") (pintype "passive"))
      (node (ref "VR1") (pin "3") (pinfunction "E_3") (pintype "passive"))
      (node (ref "~NUDEV~1") (pin "GND") (pinfunction "GND_GND") (pintype "power_in"))
    )
    (net (code "11") (name "GND2") (class "Default")
      (node (ref "C32") (pin "2") (pinfunction "2_2") (pintype "passive"))
      (node (ref "C33") (pin "-") (pinfunction "-_-") (pintype "passive"))
      (node (ref "J1") (pin "5") (pinfunction "5_5") (pintype "passive"))
      (node (ref "OK2") (pin "2") (pinfunction "C_2") (pintype "passive"))
      (node (ref "ONOFF2") (pin "MP") (pinfunction "MP_MP") (pintype "passive"))
      (node (ref "Q5") (pin "1") (pinfunction "E_1") (pintype "passive"))
      (node (ref "R41") (pin "1") (pinfunction "1_1") (pintype "passive"))
      (node (ref "U2") (pin "4") (pinfunction "GND_4") (pintype "passive"))
      (node (ref "~NUDEV~1") (pin "GNDA") (pinfunction "GNDA_GNDA") (pintype "power_in"))
    )
    (net (code "12") (name "IN") (class "Default")
      (node (ref "IN_JACK") (pin "T") (pinfunction "T_T") (pintype "passive"))
      (node (ref "K2") (pin "4") (pinfunction "S_4") (pintype "passive"))
      (node (ref "U$9") (pin "1A") (pinfunction "1A_1A") (pintype "passive"))
      (node (ref "U$9") (pin "3B") (pinfunction "3B_3B") (pintype "passive"))
    )
    (net (code "13") (name "Net-(++-PadMP)") (class "Default")
      (node (ref "++") (pin "MP") (pinfunction "MP_MP") (pintype "passive"))
      (node (ref "F1") (pin "1") (pinfunction "1_1") (pintype "bidirectional"))
    )
    (net (code "14") (name "Net-(C8-Pad2)") (class "Default")
      (node (ref "C8") (pin "2") (pinfunction "2_2") (pintype "passive"))
      (node (ref "DIODES") (pin "4") (pinfunction "4_4") (pintype "passive"))
    )
    (net (code "15") (name "Net-(C9-Pad2)") (class "Default")
      (node (ref "C9") (pin "2") (pinfunction "2_2") (pintype "passive"))
      (node (ref "U$1") (pin "C") (pinfunction "C_C") (pintype "passive"))
      (node (ref "U$2") (pin "A") (pinfunction "A_A") (pintype "passive"))
    )
    (net (code "16") (name "Net-(C10-Pad+)") (class "Default")
      (node (ref "C10") (pin "+") (pinfunction "+_+") (pintype "passive"))
      (node (ref "R13") (pin "2") (pinfunction "2_2") (pintype "passive"))
    )
    (net (code "17") (name "Net-(C13-Pad-)") (class "Default")
      (node (ref "C13") (pin "-") (pinfunction "-_-") (pintype "passive"))
      (node (ref "R33") (pin "1") (pinfunction "1_1") (pintype "passive"))
    )
    (net (code "18") (name "Net-(C18-Pad1)") (class "Default")
      (node (ref "C18") (pin "1") (pinfunction "1_1") (pintype "passive"))
      (node (ref "R25") (pin "2") (pinfunction "2_2") (pintype "passive"))
    )
    (net (code "19") (name "Net-(C18-Pad2)") (class "Default")
      (node (ref "C18") (pin "2") (pinfunction "2_2") (pintype "passive"))
      (node (ref "R60") (pin "1") (pinfunction "1_1") (pintype "passive"))
    )
    (net (code "20") (name "Net-(C28-Pad1)") (class "Default")
      (node (ref "C28") (pin "1") (pinfunction "1_1") (pintype "passive"))
      (node (ref "U$19") (pin "A") (pinfunction "A_A") (pintype "passive"))
      (node (ref "U$20") (pin "C") (pinfunction "C_C") (pintype "passive"))
    )
    (net (code "21") (name "Net-(C28-Pad2)") (class "Default")
      (node (ref "C28") (pin "2") (pinfunction "2_2") (pintype "passive"))
      (node (ref "R2") (pin "A") (pinfunction "A_A") (pintype "passive"))
      (node (ref "R2") (pin "S") (pinfunction "S_S") (pintype "passive"))
    )
    (net (code "22") (name "Net-(C37-Pad1)") (class "Default")
      (node (ref "C37") (pin "1") (pinfunction "1_1") (pintype "passive"))
      (node (ref "U$11") (pin "A") (pinfunction "A_A") (pintype "passive"))
      (node (ref "U$5") (pin "C") (pinfunction "C_C") (pintype "passive"))
    )
    (net (code "23") (name "Net-(DIODES-5)") (class "Default")
      (node (ref "C14") (pin "-") (pinfunction "-_-") (pintype "passive"))
      (node (ref "C29") (pin "1") (pinfunction "1_1") (pintype "passive"))
      (node (ref "DIODES") (pin "6") (pinfunction "5_6") (pintype "passive"))
      (node (ref "Q4") (pin "3") (pinfunction "C_3") (pintype "passive"))
      (node (ref "R20") (pin "1") (pinfunction "1_1") (pintype "passive"))
      (node (ref "R21") (pin "2") (pinfunction "2_2") (pintype "passive"))
      (node (ref "U$3") (pin "A") (pinfunction "A_A") (pintype "passive"))
      (node (ref "U$4") (pin "C") (pinfunction "C_C") (pintype "passive"))
    )
    (net (code "24") (name "Net-(FILTER-3A)") (class "Default")
      (node (ref "C12") (pin "2") (pinfunction "2_2") (pintype "passive"))
      (node (ref "C23") (pin "2") (pinfunction "2_2") (pintype "passive"))
      (node (ref "FILTER") (pin "1/3") (pinfunction "3A_1/3") (pintype "passive"))
      (node (ref "FILTER") (pin "2/3") (pinfunction "3B_2/3") (pintype "passive"))
    )
    (net (code "25") (name "Net-(HEIGHT-2)") (class "Default")
      (node (ref "HEIGHT") (pin "3") (pinfunction "2_3") (pintype "passive"))
      (node (ref "R1") (pin "2") (pinfunction "2_2") (pintype "passive"))
      (node (ref "R31") (pin "3") (pinfunction "E_3") (pintype "passive"))
      (node (ref "R32") (pin "3") (pinfunction "E_3") (pintype "passive"))
      (node (ref "R39") (pin "2") (pinfunction "2_2") (pintype "passive"))
    )
    (net (code "26") (name "Net-(HEIGHT-3)") (class "Default")
      (node (ref "HEIGHT") (pin "2") (pinfunction "3_2") (pintype "passive"))
      (node (ref "R15") (pin "2") (pinfunction "S_2") (pintype "passive"))
    )
    (net (code "27") (name "Net-(IC1A--IN)") (class "Default")
      (node (ref "C21") (pin "1") (pinfunction "1_1") (pintype "passive"))
      (node (ref "IC1") (pin "2") (pinfunction "-IN_2") (pintype "input"))
      (node (ref "R29") (pin "2") (pinfunction "2_2") (pintype "passive"))
      (node (ref "R58") (pin "1") (pinfunction "1_1") (pintype "passive"))
    )
    (net (code "28") (name "Net-(IC1A-OUT)") (class "Default")
      (node (ref "C21") (pin "2") (pinfunction "2_2") (pintype "passive"))
      (node (ref "IC1") (pin "1") (pinfunction "OUT_1") (pintype "output"))
      (node (ref "OD_LEVEL2") (pin "6") (pinfunction "5_6") (pintype "passive"))
      (node (ref "R29") (pin "1") (pinfunction "1_1") (pintype "passive"))
    )
    (net (code "29") (name "Net-(IC1B--IN)") (class "Default")
      (node (ref "IC1") (pin "6") (pinfunction "-IN_6") (pintype "input"))
      (node (ref "R25") (pin "1") (pinfunction "1_1") (pintype "passive"))
      (node (ref "R26") (pin "2") (pinfunction "2_2") (pintype "passive"))
    )
    (net (code "30") (name "Net-(IC1B-OUT)") (class "Default")
      (node (ref "IC1") (pin "7") (pinfunction "OUT_7") (pintype "output"))
      (node (ref "OD_LEVEL1") (pin "6") (pinfunction "5_6") (pintype "passive"))
      (node (ref "R26") (pin "1") (pinfunction "1_1") (pintype "passive"))
    )
    (net (code "31") (name "Net-(IC1C-+IN)") (class "Default")
      (node (ref "C1") (pin "2") (pinfunction "2_2") (pintype "passive"))
      (node (ref "IC1") (pin "10") (pinfunction "+IN_10") (pintype "input"))
      (node (ref "R6") (pin "2") (pinfunction "2_2") (pintype "passive"))
    )
    (net (code "32") (name "Net-(IC1C--IN)") (class "Default")
      (node (ref "C25") (pin "+") (pinfunction "+_+") (pintype "passive"))
      (node (ref "IC1") (pin "8") (pinfunction "OUT_8") (pintype "output"))
      (node (ref "IC1") (pin "9") (pinfunction "-IN_9") (pintype "input"))
      (node (ref "R58") (pin "2") (pinfunction "2_2") (pintype "passive"))
      (node (ref "R60") (pin "2") (pinfunction "2_2") (pintype "passive"))
      (node (ref "R7") (pin "2") (pinfunction "2_2") (pintype "passive"))
    )
    (net (code "33") (name "Net-(IC1D-+IN)") (class "Default")
      (node (ref "IC1") (pin "12") (pinfunction "+IN_12") (pintype "input"))
      (node (ref "R7") (pin "1") (pinfunction "1_1") (pintype "passive"))
    )
    (net (code "34") (name "Net-(IC1D--IN)") (class "Default")
      (node (ref "C4") (pin "1") (pinfunction "1_1") (pintype "passive"))
      (node (ref "IC1") (pin "13") (pinfunction "-IN_13") (pintype "input"))
      (node (ref "IC1") (pin "14") (pinfunction "OUT_14") (pintype "output"))
    )
    (net (code "35") (name "Net-(IC2A-+IN)") (class "Default")
      (node (ref "C16") (pin "2") (pinfunction "2_2") (pintype "passive"))
      (node (ref "IC2") (pin "3") (pinfunction "+IN_3") (pintype "input"))
      (node (ref "R39") (pin "1") (pinfunction "1_1") (pintype "passive"))
      (node (ref "R53") (pin "2") (pinfunction "2_2") (pintype "passive"))
    )
    (net (code "36") (name "Net-(IC2A--IN)") (class "Default")
      (node (ref "IC2") (pin "2") (pinfunction "-IN_2") (pintype "input"))
      (node (ref "R40") (pin "2") (pinfunction "2_2") (pintype "passive"))
      (node (ref "R42") (pin "1") (pinfunction "1_1") (pintype "passive"))
    )
    (net (code "37") (name "Net-(IC2A-OUT)") (class "Default")
      (node (ref "IC2") (pin "1") (pinfunction "OUT_1") (pintype "output"))
      (node (ref "R1") (pin "1") (pinfunction "1_1") (pintype "passive"))
      (node (ref "R40") (pin "1") (pinfunction "1_1") (pintype "passive"))
    )
    (net (code "38") (name "Net-(IC2B-+IN)") (class "Default")
      (node (ref "IC2") (pin "5") (pinfunction "+IN_5") (pintype "input"))
      (node (ref "R53") (pin "1") (pinfunction "1_1") (pintype "passive"))
      (node (ref "WIDTH") (pin "3") (pinfunction "2_3") (pintype "passive"))
    )
    (net (code "39") (name "Net-(IC2B--IN)") (class "Default")
      (node (ref "C17") (pin "2") (pinfunction "2_2") (pintype "passive"))
      (node (ref "IC2") (pin "6") (pinfunction "-IN_6") (pintype "input"))
      (node (ref "R43") (pin "1") (pinfunction "1_1") (pintype "passive"))
    )
    (net (code "40") (name "Net-(IC2B-OUT)") (class "Default")
      (node (ref "C17") (pin "1") (pinfunction "1_1") (pintype "passive"))
      (node (ref "IC2") (pin "7") (pinfunction "OUT_7") (pintype "output"))
      (node (ref "R42") (pin "2") (pinfunction "2_2") (pintype "passive"))
      (node (ref "R44") (pin "1") (pinfunction "1_1") (pintype "passive"))
    )
    (net (code "41") (name "Net-(IC2C-+IN)") (class "Default")
      (node (ref "IC2") (pin "10") (pinfunction "+IN_10") (pintype "input"))
      (node (ref "R15") (pin "3") (pinfunction "E_3") (pintype "passive"))
      (node (ref "R22") (pin "2") (pinfunction "S_2") (pintype "passive"))
      (node (ref "R23") (pin "3") (pinfunction "E_3") (pintype "passive"))
    )
    (net (code "42") (name "Net-(IC2C--IN)") (class "Default")
      (node (ref "C36") (pin "2") (pinfunction "2_2") (pintype "passive"))
      (node (ref "IC2") (pin "9") (pinfunction "-IN_9") (pintype "input"))
      (node (ref "R15") (pin "1") (pinfunction "A_1") (pintype "passive"))
      (node (ref "R23") (pin "1") (pinfunction "A_1") (pintype "passive"))
      (node (ref "R30") (pin "2") (pinfunction "2_2") (pintype "passive"))
    )
    (net (code "43") (name "Net-(IC2D--IN)") (class "Default")
      (node (ref "IC2") (pin "13") (pinfunction "-IN_13") (pintype "input"))
      (node (ref "R24") (pin "2") (pinfunction "S_2") (pintype "passive"))
      (node (ref "R27") (pin "3") (pinfunction "E_3") (pintype "passive"))
      (node (ref "R28") (pin "3") (pinfunction "E_3") (pintype "passive"))
      (node (ref "R36") (pin "2") (pinfunction "S_2") (pintype "passive"))
      (node (ref "R36") (pin "3") (pinfunction "E_3") (pintype "passive"))
      (node (ref "U$19") (pin "C") (pinfunction "C_C") (pintype "passive"))
      (node (ref "U$20") (pin "A") (pinfunction "A_A") (pintype "passive"))
    )
    (net (code "44") (name "Net-(IC2D-OUT)") (class "Default")
      (node (ref "C24") (pin "+") (pinfunction "+_+") (pintype "passive"))
      (node (ref "IC2") (pin "14") (pinfunction "OUT_14") (pintype "output"))
      (node (ref "R2") (pin "E") (pinfunction "E_E") (pintype "passive"))
      (node (ref "R36") (pin "1") (pinfunction "A_1") (pintype "passive"))
    )
    (net (code "45") (name "Net-(IC3-+IN)") (class "Default")
      (node (ref "C2") (pin "+") (pinfunction "+_+") (pintype "passive"))
      (node (ref "IC3") (pin "3") (pinfunction "+IN_3") (pintype "input"))
      (node (ref "R3") (pin "1") (pinfunction "1_1") (pintype "passive"))
      (node (ref "R4") (pin "1") (pinfunction "1_1") (pintype "passive"))
    )
    (net (code "46") (name "Net-(K2B-O)") (class "Default")
      (node (ref "K2") (pin "7") (pinfunction "O_7") (pintype "passive"))
      (node (ref "U$9") (pin "2A") (pinfunction "2A_2A") (pintype "passive"))
    )
    (net (code "47") (name "Net-(K2C--)") (class "Default")
      (node (ref "D1") (pin "A") (pinfunction "A_A") (pintype "passive"))
      (node (ref "K2") (pin "8") (pinfunction "-_8") (pintype "passive"))
      (node (ref "LED2") (pin "K") (pinfunction "C_K") (pintype "passive"))
      (node (ref "Q5") (pin "3") (pinfunction "C_3") (pintype "passive"))
    )
    (net (code "48") (name "Net-(LED2-PadA)") (class "Default")
      (node (ref "LED2") (pin "A") (pinfunction "A_A") (pintype "passive"))
      (node (ref "R38") (pin "1") (pinfunction "1_1") (pintype "passive"))
    )
    (net (code "49") (name "Net-(OD_LEVEL-5)") (class "Default")
      (node (ref "C4") (pin "2") (pinfunction "2_2") (pintype "passive"))
      (node (ref "OD_LEVEL") (pin "5") (pinfunction "6_5") (pintype "passive"))
      (node (ref "OD_LEVEL") (pin "6") (pinfunction "5_6") (pintype "passive"))
      (node (ref "R9") (pin "2") (pinfunction "2_2") (pintype "passive"))
    )
    (net (code "50") (name "Net-(OD_LEVEL-Pad4)") (class "Default")
      (node (ref "OD_LEVEL") (pin "4") (pinfunction "4_4") (pintype "passive"))
      (node (ref "R8") (pin "2") (pinfunction "2_2") (pintype "passive"))
    )
    (net (code "51") (name "Net-(OD_LEVEL1-6)") (class "Default")
      (node (ref "C19") (pin "+") (pinfunction "+_+") (pintype "passive"))
      (node (ref "OD_LEVEL1") (pin "5") (pinfunction "6_5") (pintype "passive"))
    )
    (net (code "52") (name "Net-(OD_LEVEL2-6)") (class "Default")
      (node (ref "C22") (pin "+") (pinfunction "+_+") (pintype "passive"))
      (node (ref "OD_LEVEL2") (pin "5") (pinfunction "6_5") (pintype "passive"))
    )
    (net (code "53") (name "Net-(OK2-A)") (class "Default")
      (node (ref "OK2") (pin "1") (pinfunction "A_1") (pintype "passive"))
      (node (ref "R46") (pin "1") (pinfunction "1_1") (pintype "passive"))
    )
    (net (code "54") (name "Net-(Q1-B)") (class "Default")
      (node (ref "C7") (pin "2") (pinfunction "2_2") (pintype "passive"))
      (node (ref "C9") (pin "1") (pinfunction "1_1") (pintype "passive"))
      (node (ref "Q1") (pin "2") (pinfunction "B_2") (pintype "passive"))
      (node (ref "R10") (pin "2") (pinfunction "2_2") (pintype "passive"))
    )
    (net (code "55") (name "Net-(Q1-C)") (class "Default")
      (node (ref "C10") (pin "-") (pinfunction "-_-") (pintype "passive"))
      (node (ref "Q1") (pin "3") (pinfunction "C_3") (pintype "passive"))
      (node (ref "R10") (pin "1") (pinfunction "1_1") (pintype "passive"))
      (node (ref "R12") (pin "2") (pinfunction "2_2") (pintype "passive"))
      (node (ref "R17") (pin "2") (pinfunction "2_2") (pintype "passive"))
      (node (ref "U$2") (pin "C") (pinfunction "C_C") (pintype "passive"))
    )
    (net (code "56") (name "Net-(Q1-E)") (class "Default")
      (node (ref "C6") (pin "+") (pinfunction "+_+") (pintype "passive"))
      (node (ref "Q1") (pin "1") (pinfunction "E_1") (pintype "passive"))
      (node (ref "Q2") (pin "3") (pinfunction "E_3") (pintype "passive"))
    )
    (net (code "57") (name "Net-(Q2-B)") (class "Default")
      (node (ref "C5") (pin "+") (pinfunction "+_+") (pintype "passive"))
      (node (ref "Q2") (pin "2") (pinfunction "B_2") (pintype "passive"))
      (node (ref "R11") (pin "1") (pinfunction "1_1") (pintype "passive"))
    )
    (net (code "58") (name "Net-(Q2-C)") (class "Default")
      (node (ref "C7") (pin "1") (pinfunction "1_1") (pintype "passive"))
      (node (ref "Q2") (pin "1") (pinfunction "C_1") (pintype "passive"))
      (node (ref "R11") (pin "2") (pinfunction "2_2") (pintype "passive"))
      (node (ref "R16") (pin "1") (pinfunction "1_1") (pintype "passive"))
    )
    (net (code "59") (name "Net-(Q3-B)") (class "Default")
      (node (ref "C27") (pin "2") (pinfunction "2_2") (pintype "passive"))
      (node (ref "Q3") (pin "2") (pinfunction "B_2") (pintype "passive"))
      (node (ref "R19") (pin "1") (pinfunction "1_1") (pintype "passive"))
      (node (ref "VR1") (pin "2") (pinfunction "S_2") (pintype "passive"))
    )
    (net (code "60") (name "Net-(Q3-C)") (class "Default")
      (node (ref "C27") (pin "1") (pinfunction "1_1") (pintype "passive"))
      (node (ref "C3") (pin "1") (pinfunction "1_1") (pintype "passive"))
      (node (ref "Q3") (pin "1") (pinfunction "C_1") (pintype "passive"))
      (node (ref "R18") (pin "1") (pinfunction "1_1") (pintype "passive"))
      (node (ref "R19") (pin "2") (pinfunction "2_2") (pintype "passive"))
    )
    (net (code "61") (name "Net-(Q3-E)") (class "Default")
      (node (ref "C11") (pin "+") (pinfunction "+_+") (pintype "passive"))
      (node (ref "Q3") (pin "3") (pinfunction "E_3") (pintype "passive"))
      (node (ref "Q4") (pin "1") (pinfunction "E_1") (pintype "passive"))
    )
    (net (code "62") (name "Net-(Q4-B)") (class "Default")
      (node (ref "C29") (pin "2") (pinfunction "2_2") (pintype "passive"))
      (node (ref "C3") (pin "2") (pinfunction "2_2") (pintype "passive"))
      (node (ref "C8") (pin "1") (pinfunction "1_1") (pintype "passive"))
      (node (ref "Q4") (pin "2") (pinfunction "B_2") (pintype "passive"))
      (node (ref "R20") (pin "2") (pinfunction "2_2") (pintype "passive"))
      (node (ref "U$3") (pin "C") (pinfunction "C_C") (pintype "passive"))
      (node (ref "U$4") (pin "A") (pinfunction "A_A") (pintype "passive"))
    )
    (net (code "63") (name "Net-(Q5-B)") (class "Default")
      (node (ref "Q5") (pin "2") (pinfunction "B_2") (pintype "passive"))
      (node (ref "R41") (pin "2") (pinfunction "2_2") (pintype "passive"))
      (node (ref "R45") (pin "1") (pinfunction "1_1") (pintype "passive"))
    )
    (net (code "64") (name "Net-(R12-Pad1)") (class "Default")
      (node (ref "R12") (pin "1") (pinfunction "1_1") (pintype "passive"))
      (node (ref "U$1") (pin "A") (pinfunction "A_A") (pintype "passive"))
    )
    (net (code "65") (name "Net-(R22-A)") (class "Default")
      (node (ref "C14") (pin "+") (pinfunction "+_+") (pintype "passive"))
      (node (ref "R22") (pin "1") (pinfunction "A_1") (pintype "passive"))
    )
    (net (code "66") (name "Net-(R23-S)") (class "Default")
      (node (ref "HEIGHT") (pin "1") (pinfunction "1_1") (pintype "passive"))
      (node (ref "R23") (pin "2") (pinfunction "S_2") (pintype "passive"))
    )
    (net (code "67") (name "Net-(R24-A)") (class "Default")
      (node (ref "C15") (pin "-") (pinfunction "-_-") (pintype "passive"))
      (node (ref "R24") (pin "1") (pinfunction "A_1") (pintype "passive"))
    )
    (net (code "68") (name "Net-(R27-A)") (class "Default")
      (node (ref "C19") (pin "-") (pinfunction "-_-") (pintype "passive"))
      (node (ref "R27") (pin "1") (pinfunction "A_1") (pintype "passive"))
      (node (ref "R27") (pin "2") (pinfunction "S_2") (pintype "passive"))
    )
    (net (code "69") (name "Net-(R28-A)") (class "Default")
      (node (ref "C22") (pin "-") (pinfunction "-_-") (pintype "passive"))
      (node (ref "R28") (pin "1") (pinfunction "A_1") (pintype "passive"))
      (node (ref "R28") (pin "2") (pinfunction "S_2") (pintype "passive"))
    )
    (net (code "70") (name "Net-(R31-A)") (class "Default")
      (node (ref "C13") (pin "+") (pinfunction "+_+") (pintype "passive"))
      (node (ref "R31") (pin "1") (pinfunction "A_1") (pintype "passive"))
      (node (ref "R32") (pin "1") (pinfunction "A_1") (pintype "passive"))
    )
    (net (code "71") (name "Net-(R31-S)") (class "Default")
      (node (ref "R31") (pin "2") (pinfunction "S_2") (pintype "passive"))
      (node (ref "WIDTH") (pin "2") (pinfunction "3_2") (pintype "passive"))
    )
    (net (code "72") (name "Net-(R32-S)") (class "Default")
      (node (ref "R32") (pin "2") (pinfunction "S_2") (pintype "passive"))
      (node (ref "WIDTH") (pin "1") (pinfunction "1_1") (pintype "passive"))
    )
    (net (code "73") (name "Net-(THE_GAIN-A)") (class "Default")
      (node (ref "R9") (pin "1") (pinfunction "1_1") (pintype "passive"))
      (node (ref "THE_GAIN") (pin "P$3") (pinfunction "A_P$3") (pintype "passive"))
    )
    (net (code "74") (name "Net-(THE_GAIN-E)") (class "Default")
      (node (ref "R37") (pin "2") (pinfunction "2_2") (pintype "passive"))
      (node (ref "THE_GAIN") (pin "P$1") (pinfunction "E_P$1") (pintype "passive"))
    )
    (net (code "75") (name "Net-(THE_GAIN-S)") (class "Default")
      (node (ref "C5") (pin "-") (pinfunction "-_-") (pintype "passive"))
      (node (ref "THE_GAIN") (pin "P$2") (pinfunction "S_P$2") (pintype "passive"))
    )
    (net (code "76") (name "Net-(U2-PB0)") (class "Default")
      (node (ref "J1") (pin "3") (pinfunction "3_3") (pintype "passive"))
      (node (ref "U2") (pin "5") (pinfunction "PB0_5") (pintype "bidirectional"))
    )
    (net (code "77") (name "Net-(U2-PB1)") (class "Default")
      (node (ref "J1") (pin "2") (pinfunction "2_2") (pintype "passive"))
      (node (ref "R46") (pin "2") (pinfunction "2_2") (pintype "passive"))
      (node (ref "U2") (pin "6") (pinfunction "PB1_6") (pintype "bidirectional"))
    )
    (net (code "78") (name "Net-(U2-PB2)") (class "Default")
      (node (ref "J1") (pin "4") (pinfunction "4_4") (pintype "passive"))
      (node (ref "U2") (pin "7") (pinfunction "PB2_7") (pintype "bidirectional"))
    )
    (net (code "79") (name "Net-(U2-PB3)") (class "Default")
      (node (ref "R45") (pin "2") (pinfunction "2_2") (pintype "passive"))
      (node (ref "U2") (pin "2") (pinfunction "PB3_2") (pintype "bidirectional"))
    )
    (net (code "80") (name "Net-(U2-PB4)") (class "Default")
      (node (ref "ONOFF1") (pin "MP") (pinfunction "MP_MP") (pintype "passive"))
      (node (ref "R14") (pin "1") (pinfunction "1_1") (pintype "passive"))
      (node (ref "U2") (pin "3") (pinfunction "PB4_3") (pintype "bidirectional"))
    )
    (net (code "81") (name "Net-(U2-PB5)") (class "Default")
      (node (ref "J1") (pin "6") (pinfunction "6_6") (pintype "passive"))
      (node (ref "U2") (pin "1") (pinfunction "PB5_1") (pintype "bidirectional"))
    )
    (net (code "82") (name "Net-(VOL-A)") (class "Default")
      (node (ref "C24") (pin "-") (pinfunction "-_-") (pintype "passive"))
      (node (ref "VOL") (pin "P$3") (pinfunction "A_P$3") (pintype "passive"))
    )
    (net (code "83") (name "Net-(VR1-A)") (class "Default")
      (node (ref "C37") (pin "2") (pinfunction "2_2") (pintype "passive"))
      (node (ref "R13") (pin "1") (pinfunction "1_1") (pintype "passive"))
      (node (ref "VR1") (pin "1") (pinfunction "A_1") (pintype "passive"))
    )
    (net (code "84") (name "OUT") (class "Default")
      (node (ref "K2") (pin "6") (pinfunction "P_6") (pintype "passive"))
      (node (ref "OK2") (pin "3") (pinfunction "EMIT_3") (pintype "passive"))
      (node (ref "OUT_JACK") (pin "T") (pinfunction "T_T") (pintype "passive"))
    )
    (net (code "85") (name "VB") (class "Default")
      (node (ref "C12") (pin "1") (pinfunction "1_1") (pintype "passive"))
      (node (ref "C16") (pin "1") (pinfunction "1_1") (pintype "passive"))
      (node (ref "C20") (pin "+") (pinfunction "+_+") (pintype "passive"))
      (node (ref "C23") (pin "1") (pinfunction "1_1") (pintype "passive"))
      (node (ref "C26") (pin "1") (pinfunction "1_1") (pintype "passive"))
      (node (ref "IC1") (pin "3") (pinfunction "+IN_3") (pintype "input"))
      (node (ref "IC1") (pin "5") (pinfunction "+IN_5") (pintype "input"))
      (node (ref "IC2") (pin "12") (pinfunction "+IN_12") (pintype "input"))
      (node (ref "IC3") (pin "2") (pinfunction "-IN_2") (pintype "input"))
      (node (ref "IC3") (pin "6") (pinfunction "OUT_6") (pintype "output"))
      (node (ref "R22") (pin "3") (pinfunction "E_3") (pintype "passive"))
      (node (ref "R33") (pin "2") (pinfunction "2_2") (pintype "passive"))
      (node (ref "R6") (pin "1") (pinfunction "1_1") (pintype "passive"))
    )
    (net (code "86") (name "unconnected-(DIODES-2-Pad3)") (class "Default")
      (node (ref "DIODES") (pin "3") (pinfunction "2_3") (pintype "passive"))
    )
    (net (code "87") (name "unconnected-(DIODES-3-Pad2)") (class "Default")
      (node (ref "DIODES") (pin "2") (pinfunction "3_2") (pintype "passive"))
    )
    (net (code "88") (name "unconnected-(DIODES-6-Pad5)") (class "Default")
      (node (ref "DIODES") (pin "5") (pinfunction "6_5") (pintype "passive"))
    )
    (net (code "89") (name "unconnected-(DIODES-Pad1)") (class "Default")
      (node (ref "DIODES") (pin "1") (pinfunction "1_1") (pintype "passive"))
    )
    (net (code "90") (name "unconnected-(HEIGHT-5-Pad6)") (class "Default")
      (node (ref "HEIGHT") (pin "6") (pinfunction "5_6") (pintype "passive"))
    )
    (net (code "91") (name "unconnected-(HEIGHT-6-Pad5)") (class "Default")
      (node (ref "HEIGHT") (pin "5") (pinfunction "6_5") (pintype "passive"))
    )
    (net (code "92") (name "unconnected-(HEIGHT-Pad4)") (class "Default")
      (node (ref "HEIGHT") (pin "4") (pinfunction "4_4") (pintype "passive"))
    )
    (net (code "93") (name "unconnected-(IC3-ON1-Pad1)") (class "Default")
      (node (ref "IC3") (pin "1") (pinfunction "ON1_1") (pintype "passive"))
    )
    (net (code "94") (name "unconnected-(IC3-ON2-Pad5)") (class "Default")
      (node (ref "IC3") (pin "5") (pinfunction "ON2_5") (pintype "passive"))
    )
    (net (code "95") (name "unconnected-(OD_LEVEL-2-Pad3)") (class "Default")
      (node (ref "OD_LEVEL") (pin "3") (pinfunction "2_3") (pintype "passive"))
    )
    (net (code "96") (name "unconnected-(OD_LEVEL-3-Pad2)") (class "Default")
      (node (ref "OD_LEVEL") (pin "2") (pinfunction "3_2") (pintype "passive"))
    )
    (net (code "97") (name "unconnected-(OD_LEVEL-Pad1)") (class "Default")
      (node (ref "OD_LEVEL") (pin "1") (pinfunction "1_1") (pintype "passive"))
    )
    (net (code "98") (name "unconnected-(OD_LEVEL1-2-Pad3)") (class "Default")
      (node (ref "OD_LEVEL1") (pin "3") (pinfunction "2_3") (pintype "passive"))
    )
    (net (code "99") (name "unconnected-(OD_LEVEL1-3-Pad2)") (class "Default")
      (node (ref "OD_LEVEL1") (pin "2") (pinfunction "3_2") (pintype "passive"))
    )
    (net (code "100") (name "unconnected-(OD_LEVEL1-Pad1)") (class "Default")
      (node (ref "OD_LEVEL1") (pin "1") (pinfunction "1_1") (pintype "passive"))
    )
    (net (code "101") (name "unconnected-(OD_LEVEL1-Pad4)") (class "Default")
      (node (ref "OD_LEVEL1") (pin "4") (pinfunction "4_4") (pintype "passive"))
    )
    (net (code "102") (name "unconnected-(OD_LEVEL2-2-Pad3)") (class "Default")
      (node (ref "OD_LEVEL2") (pin "3") (pinfunction "2_3") (pintype "passive"))
    )
    (net (code "103") (name "unconnected-(OD_LEVEL2-3-Pad2)") (class "Default")
      (node (ref "OD_LEVEL2") (pin "2") (pinfunction "3_2") (pintype "passive"))
    )
    (net (code "104") (name "unconnected-(OD_LEVEL2-Pad1)") (class "Default")
      (node (ref "OD_LEVEL2") (pin "1") (pinfunction "1_1") (pintype "passive"))
    )
    (net (code "105") (name "unconnected-(OD_LEVEL2-Pad4)") (class "Default")
      (node (ref "OD_LEVEL2") (pin "4") (pinfunction "4_4") (pintype "passive"))
    )
    (net (code "106") (name "unconnected-(R24-E-Pad3)") (class "Default")
      (node (ref "R24") (pin "3") (pinfunction "E_3") (pintype "passive"))
    )
    (net (code "107") (name "unconnected-(WIDTH-5-Pad6)") (class "Default")
      (node (ref "WIDTH") (pin "6") (pinfunction "5_6") (pintype "passive"))
    )
    (net (code "108") (name "unconnected-(WIDTH-6-Pad5)") (class "Default")
      (node (ref "WIDTH") (pin "5") (pinfunction "6_5") (pintype "passive"))
    )
    (net (code "109") (name "unconnected-(WIDTH-Pad4)") (class "Default")
      (node (ref "WIDTH") (pin "4") (pinfunction "4_4") (pintype "passive"))
    )
  )
)
